# SCH_picopad_2023-12-01.net
KiCad netlist of a schematic drawn in EasyEDA
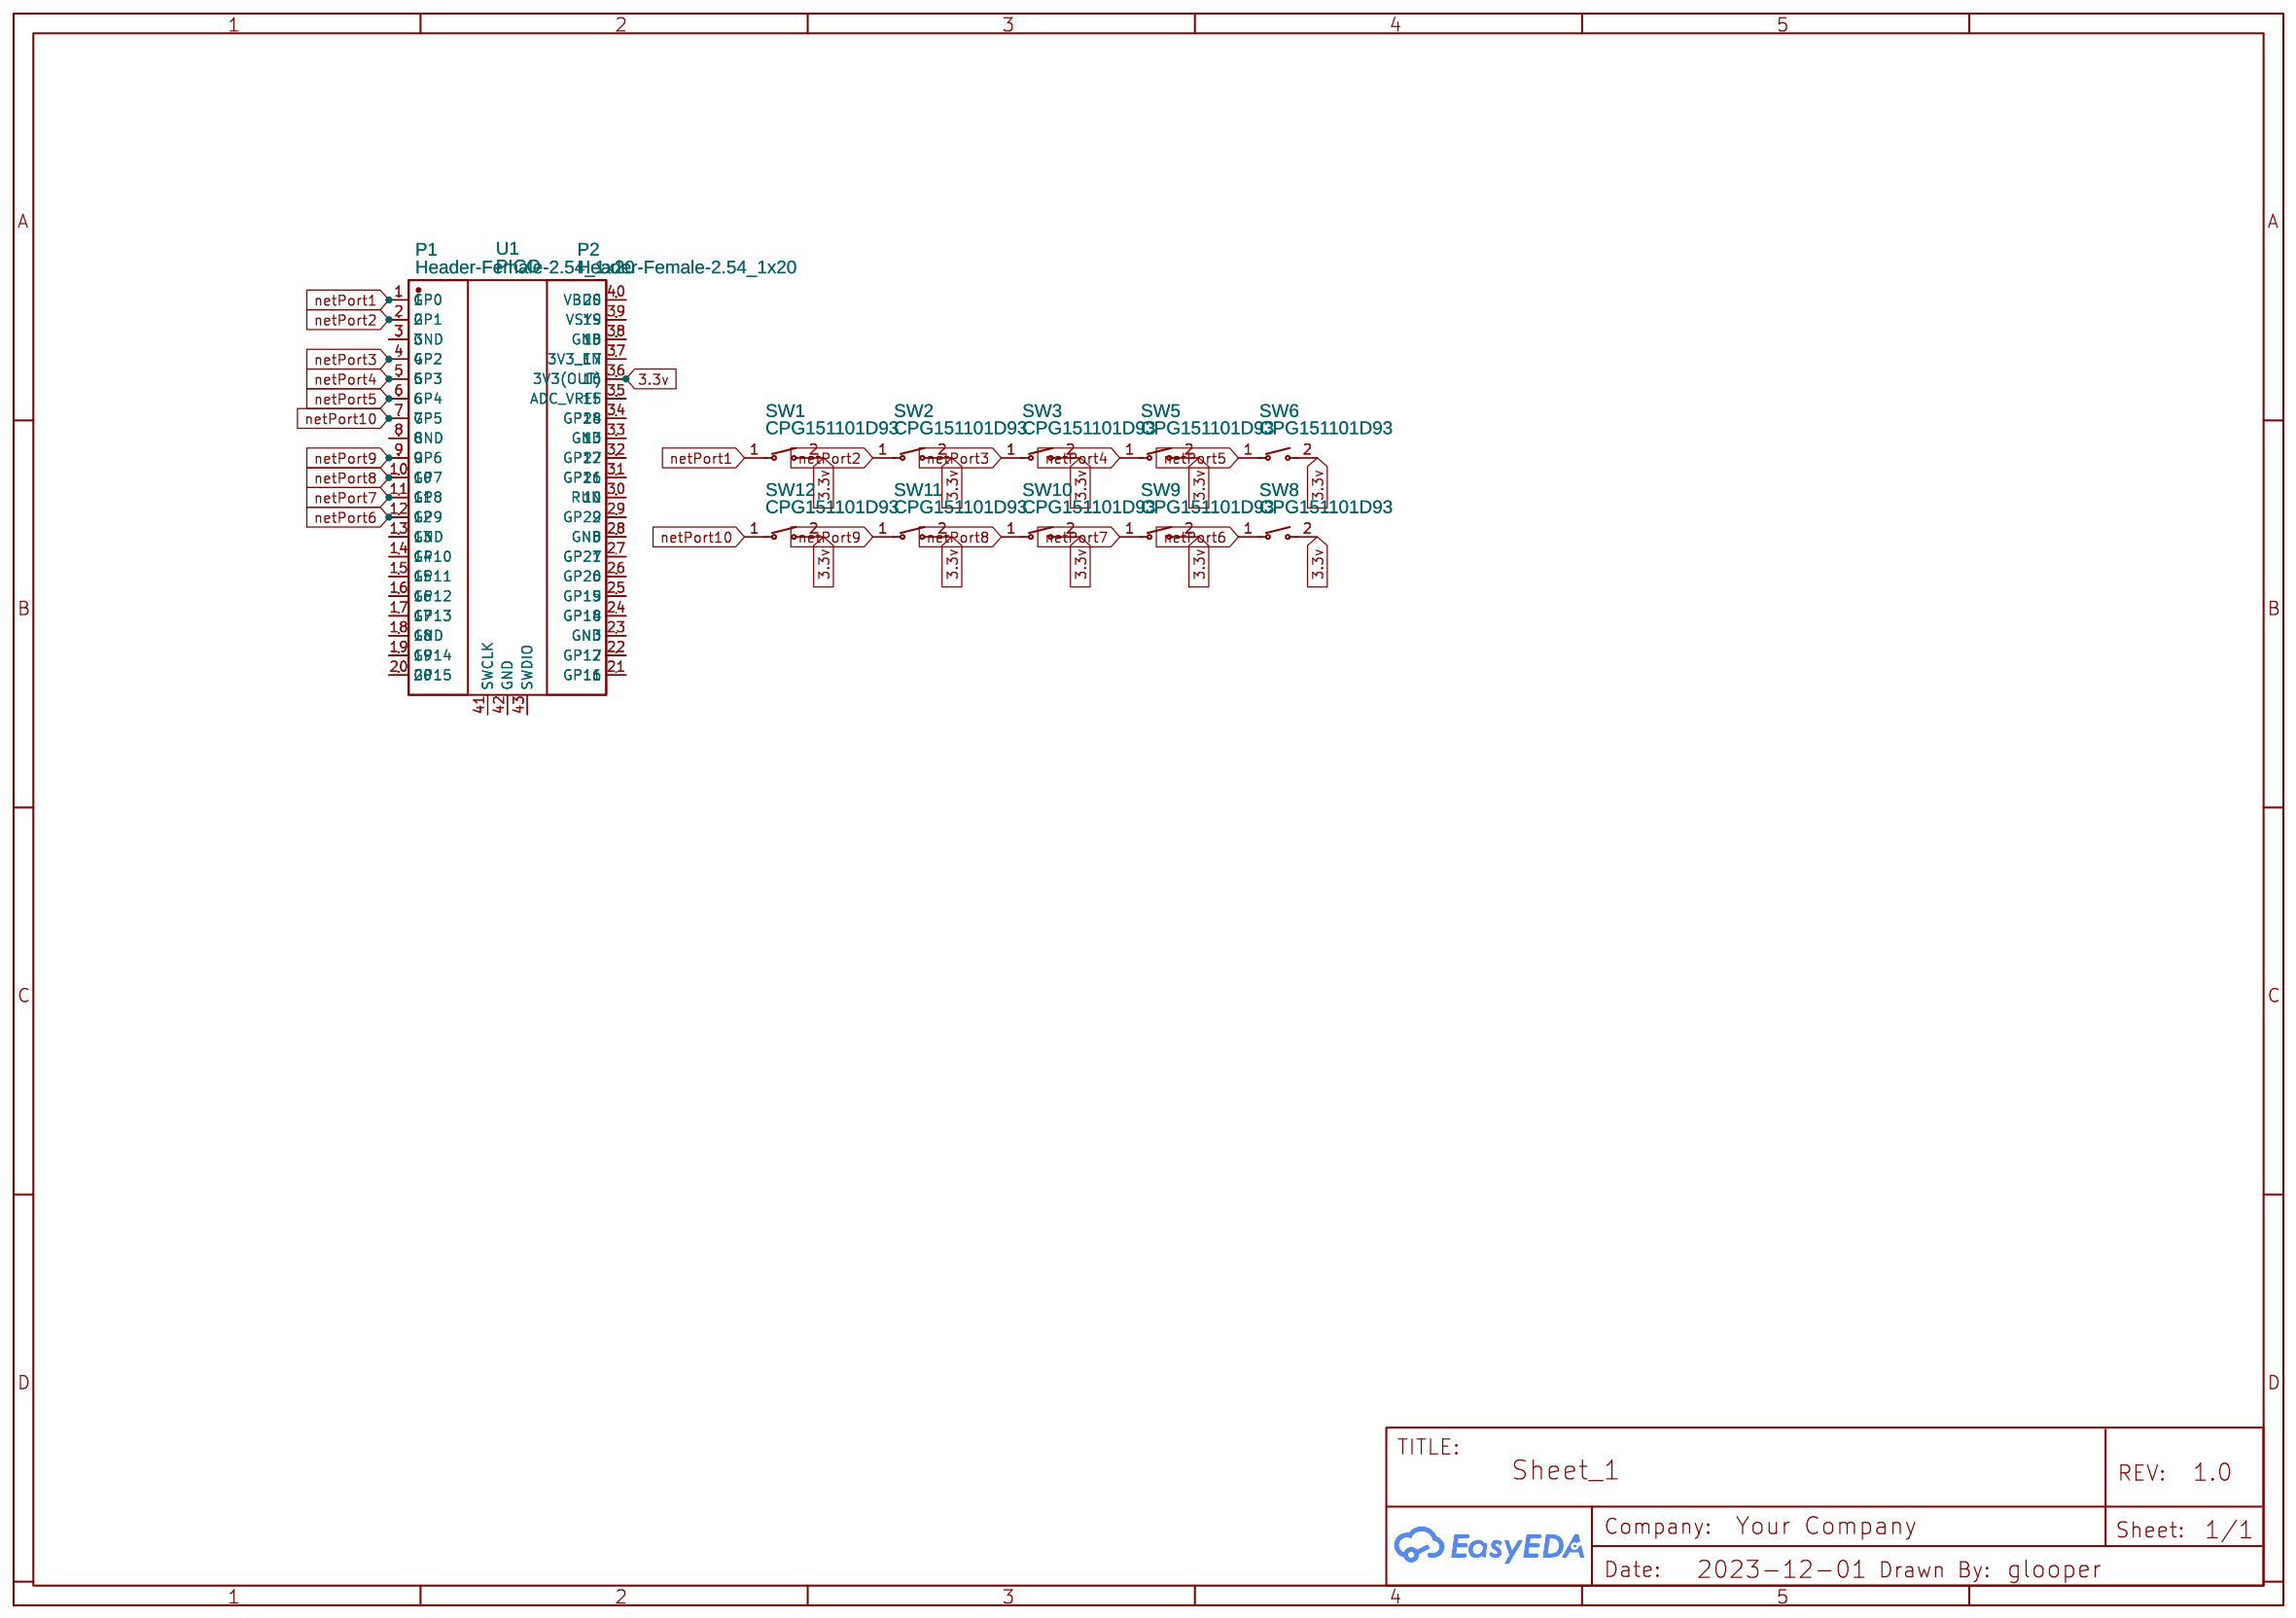
[diagram p0: schematic sheet]

(export (version "E")
  (design (tool "Eeschema 10.0.6"))
  (components
    (comp (ref "P1")
      (value "Header-Female-2.54_1x20")
      (fields (field (name "Manufacturer Part") "2.54-1*20P母") (field (name "Manufacturer") "BOOMELE(博穆精密)"))
      (libsource (lib "") (part "Header-Female-2.54_1x20_1"))
    )
    (comp (ref "P2")
      (value "Header-Female-2.54_1x20")
      (fields (field (name "Manufacturer Part") "2.54-1*20P母") (field (name "Manufacturer") "BOOMELE(博穆精密)"))
      (libsource (lib "") (part "Header-Female-2.54_1x20"))
    )
    (comp (ref "SW1")
      (value "CPG151101D93")
      (fields (field (name "Manufacturer") "Kailh(凯华)"))
      (libsource (lib "") (part "CPG151101D93"))
    )
    (comp (ref "SW2")
      (value "CPG151101D93")
      (fields (field (name "Manufacturer") "Kailh(凯华)"))
      (libsource (lib "") (part "CPG151101D93"))
    )
    (comp (ref "SW3")
      (value "CPG151101D93")
      (fields (field (name "Manufacturer") "Kailh(凯华)"))
      (libsource (lib "") (part "CPG151101D93"))
    )
    (comp (ref "SW5")
      (value "CPG151101D93")
      (fields (field (name "Manufacturer") "Kailh(凯华)"))
      (libsource (lib "") (part "CPG151101D93"))
    )
    (comp (ref "SW6")
      (value "CPG151101D93")
      (fields (field (name "Manufacturer") "Kailh(凯华)"))
      (libsource (lib "") (part "CPG151101D93"))
    )
    (comp (ref "SW8")
      (value "CPG151101D93")
      (fields (field (name "Manufacturer") "Kailh(凯华)"))
      (libsource (lib "") (part "CPG151101D93"))
    )
    (comp (ref "SW9")
      (value "CPG151101D93")
      (fields (field (name "Manufacturer") "Kailh(凯华)"))
      (libsource (lib "") (part "CPG151101D93"))
    )
    (comp (ref "SW10")
      (value "CPG151101D93")
      (fields (field (name "Manufacturer") "Kailh(凯华)"))
      (libsource (lib "") (part "CPG151101D93"))
    )
    (comp (ref "SW11")
      (value "CPG151101D93")
      (fields (field (name "Manufacturer") "Kailh(凯华)"))
      (libsource (lib "") (part "CPG151101D93"))
    )
    (comp (ref "SW12")
      (value "CPG151101D93")
      (fields (field (name "Manufacturer") "Kailh(凯华)"))
      (libsource (lib "") (part "CPG151101D93"))
    )
    (comp (ref "U1")
      (value "PICO")
      (fields (field (name "Manufacturer") "Raspberry Pi(树莓派)"))
      (libsource (lib "") (part "PICO"))
    )
  )
  (nets
    (net (code "1") (name "3.3v") (class "Default")
      (node (ref "P2") (pin "16") (pinfunction "16_16") (pintype "input"))
      (node (ref "SW1") (pin "2") (pinfunction "2_2") (pintype "unspecified"))
      (node (ref "SW10") (pin "2") (pinfunction "2_2") (pintype "unspecified"))
      (node (ref "SW11") (pin "2") (pinfunction "2_2") (pintype "unspecified"))
      (node (ref "SW12") (pin "2") (pinfunction "2_2") (pintype "unspecified"))
      (node (ref "SW2") (pin "2") (pinfunction "2_2") (pintype "unspecified"))
      (node (ref "SW3") (pin "2") (pinfunction "2_2") (pintype "unspecified"))
      (node (ref "SW5") (pin "2") (pinfunction "2_2") (pintype "unspecified"))
      (node (ref "SW6") (pin "2") (pinfunction "2_2") (pintype "unspecified"))
      (node (ref "SW8") (pin "2") (pinfunction "2_2") (pintype "unspecified"))
      (node (ref "SW9") (pin "2") (pinfunction "2_2") (pintype "unspecified"))
      (node (ref "U1") (pin "36") (pinfunction "3V3(OUT)_36") (pintype "unspecified"))
    )
    (net (code "2") (name "Net-(P1-Pad3)") (class "Default")
      (node (ref "P1") (pin "3") (pinfunction "3_3") (pintype "input"))
      (node (ref "U1") (pin "3") (pinfunction "GND_3") (pintype "unspecified"))
    )
    (net (code "3") (name "Net-(P1-Pad8)") (class "Default")
      (node (ref "P1") (pin "8") (pinfunction "8_8") (pintype "input"))
      (node (ref "U1") (pin "8") (pinfunction "GND_8") (pintype "unspecified"))
    )
    (net (code "4") (name "Net-(P1-Pad13)") (class "Default")
      (node (ref "P1") (pin "13") (pinfunction "13_13") (pintype "input"))
      (node (ref "U1") (pin "13") (pinfunction "GND_13") (pintype "unspecified"))
    )
    (net (code "5") (name "Net-(P1-Pad18)") (class "Default")
      (node (ref "P1") (pin "18") (pinfunction "18_18") (pintype "input"))
      (node (ref "U1") (pin "18") (pinfunction "GND_18") (pintype "unspecified"))
    )
    (net (code "6") (name "Net-(P2-Pad3)") (class "Default")
      (node (ref "P2") (pin "3") (pinfunction "3_3") (pintype "input"))
      (node (ref "U1") (pin "23") (pinfunction "GND_23") (pintype "unspecified"))
    )
    (net (code "7") (name "Net-(P2-Pad8)") (class "Default")
      (node (ref "P2") (pin "8") (pinfunction "8_8") (pintype "input"))
      (node (ref "U1") (pin "28") (pinfunction "GND_28") (pintype "unspecified"))
    )
    (net (code "8") (name "Net-(P2-Pad13)") (class "Default")
      (node (ref "P2") (pin "13") (pinfunction "13_13") (pintype "input"))
      (node (ref "U1") (pin "33") (pinfunction "GND_33") (pintype "unspecified"))
    )
    (net (code "9") (name "Net-(P2-Pad18)") (class "Default")
      (node (ref "P2") (pin "18") (pinfunction "18_18") (pintype "input"))
      (node (ref "U1") (pin "38") (pinfunction "GND_38") (pintype "unspecified"))
    )
    (net (code "10") (name "Net-(U1-3V3_EN)") (class "Default")
      (node (ref "P2") (pin "17") (pinfunction "17_17") (pintype "input"))
      (node (ref "U1") (pin "37") (pinfunction "3V3_EN_37") (pintype "unspecified"))
    )
    (net (code "11") (name "Net-(U1-ADC_VREF)") (class "Default")
      (node (ref "P2") (pin "15") (pinfunction "15_15") (pintype "input"))
      (node (ref "U1") (pin "35") (pinfunction "ADC_VREF_35") (pintype "unspecified"))
    )
    (net (code "12") (name "Net-(U1-GP10)") (class "Default")
      (node (ref "P1") (pin "14") (pinfunction "14_14") (pintype "input"))
      (node (ref "U1") (pin "14") (pinfunction "GP10_14") (pintype "unspecified"))
    )
    (net (code "13") (name "Net-(U1-GP11)") (class "Default")
      (node (ref "P1") (pin "15") (pinfunction "15_15") (pintype "input"))
      (node (ref "U1") (pin "15") (pinfunction "GP11_15") (pintype "unspecified"))
    )
    (net (code "14") (name "Net-(U1-GP12)") (class "Default")
      (node (ref "P1") (pin "16") (pinfunction "16_16") (pintype "input"))
      (node (ref "U1") (pin "16") (pinfunction "GP12_16") (pintype "unspecified"))
    )
    (net (code "15") (name "Net-(U1-GP13)") (class "Default")
      (node (ref "P1") (pin "17") (pinfunction "17_17") (pintype "input"))
      (node (ref "U1") (pin "17") (pinfunction "GP13_17") (pintype "unspecified"))
    )
    (net (code "16") (name "Net-(U1-GP14)") (class "Default")
      (node (ref "P1") (pin "19") (pinfunction "19_19") (pintype "input"))
      (node (ref "U1") (pin "19") (pinfunction "GP14_19") (pintype "unspecified"))
    )
    (net (code "17") (name "Net-(U1-GP15)") (class "Default")
      (node (ref "P1") (pin "20") (pinfunction "20_20") (pintype "input"))
      (node (ref "U1") (pin "20") (pinfunction "GP15_20") (pintype "unspecified"))
    )
    (net (code "18") (name "Net-(U1-GP16)") (class "Default")
      (node (ref "P2") (pin "1") (pinfunction "1_1") (pintype "input"))
      (node (ref "U1") (pin "21") (pinfunction "GP16_21") (pintype "unspecified"))
    )
    (net (code "19") (name "Net-(U1-GP17)") (class "Default")
      (node (ref "P2") (pin "2") (pinfunction "2_2") (pintype "input"))
      (node (ref "U1") (pin "22") (pinfunction "GP17_22") (pintype "unspecified"))
    )
    (net (code "20") (name "Net-(U1-GP18)") (class "Default")
      (node (ref "P2") (pin "4") (pinfunction "4_4") (pintype "input"))
      (node (ref "U1") (pin "24") (pinfunction "GP18_24") (pintype "unspecified"))
    )
    (net (code "21") (name "Net-(U1-GP19)") (class "Default")
      (node (ref "P2") (pin "5") (pinfunction "5_5") (pintype "input"))
      (node (ref "U1") (pin "25") (pinfunction "GP19_25") (pintype "unspecified"))
    )
    (net (code "22") (name "Net-(U1-GP20)") (class "Default")
      (node (ref "P2") (pin "6") (pinfunction "6_6") (pintype "input"))
      (node (ref "U1") (pin "26") (pinfunction "GP20_26") (pintype "unspecified"))
    )
    (net (code "23") (name "Net-(U1-GP21)") (class "Default")
      (node (ref "P2") (pin "7") (pinfunction "7_7") (pintype "input"))
      (node (ref "U1") (pin "27") (pinfunction "GP21_27") (pintype "unspecified"))
    )
    (net (code "24") (name "Net-(U1-GP22)") (class "Default")
      (node (ref "P2") (pin "9") (pinfunction "9_9") (pintype "input"))
      (node (ref "U1") (pin "29") (pinfunction "GP22_29") (pintype "unspecified"))
    )
    (net (code "25") (name "Net-(U1-GP26)") (class "Default")
      (node (ref "P2") (pin "11") (pinfunction "11_11") (pintype "input"))
      (node (ref "U1") (pin "31") (pinfunction "GP26_31") (pintype "unspecified"))
    )
    (net (code "26") (name "Net-(U1-GP27)") (class "Default")
      (node (ref "P2") (pin "12") (pinfunction "12_12") (pintype "input"))
      (node (ref "U1") (pin "32") (pinfunction "GP27_32") (pintype "unspecified"))
    )
    (net (code "27") (name "Net-(U1-GP28)") (class "Default")
      (node (ref "P2") (pin "14") (pinfunction "14_14") (pintype "input"))
      (node (ref "U1") (pin "34") (pinfunction "GP28_34") (pintype "unspecified"))
    )
    (net (code "28") (name "Net-(U1-RUN)") (class "Default")
      (node (ref "P2") (pin "10") (pinfunction "10_10") (pintype "input"))
      (node (ref "U1") (pin "30") (pinfunction "RUN_30") (pintype "unspecified"))
    )
    (net (code "29") (name "Net-(U1-VBUS)") (class "Default")
      (node (ref "P2") (pin "20") (pinfunction "20_20") (pintype "input"))
      (node (ref "U1") (pin "40") (pinfunction "VBUS_40") (pintype "unspecified"))
    )
    (net (code "30") (name "Net-(U1-VSYS)") (class "Default")
      (node (ref "P2") (pin "19") (pinfunction "19_19") (pintype "input"))
      (node (ref "U1") (pin "39") (pinfunction "VSYS_39") (pintype "unspecified"))
    )
    (net (code "31") (name "netPort1") (class "Default")
      (node (ref "P1") (pin "1") (pinfunction "1_1") (pintype "input"))
      (node (ref "SW1") (pin "1") (pinfunction "1_1") (pintype "unspecified"))
      (node (ref "U1") (pin "1") (pinfunction "GP0_1") (pintype "unspecified"))
    )
    (net (code "32") (name "netPort2") (class "Default")
      (node (ref "P1") (pin "2") (pinfunction "2_2") (pintype "input"))
      (node (ref "SW2") (pin "1") (pinfunction "1_1") (pintype "unspecified"))
      (node (ref "U1") (pin "2") (pinfunction "GP1_2") (pintype "unspecified"))
    )
    (net (code "33") (name "netPort3") (class "Default")
      (node (ref "P1") (pin "4") (pinfunction "4_4") (pintype "input"))
      (node (ref "SW3") (pin "1") (pinfunction "1_1") (pintype "unspecified"))
      (node (ref "U1") (pin "4") (pinfunction "GP2_4") (pintype "unspecified"))
    )
    (net (code "34") (name "netPort4") (class "Default")
      (node (ref "P1") (pin "5") (pinfunction "5_5") (pintype "input"))
      (node (ref "SW5") (pin "1") (pinfunction "1_1") (pintype "unspecified"))
      (node (ref "U1") (pin "5") (pinfunction "GP3_5") (pintype "unspecified"))
    )
    (net (code "35") (name "netPort5") (class "Default")
      (node (ref "P1") (pin "6") (pinfunction "6_6") (pintype "input"))
      (node (ref "SW6") (pin "1") (pinfunction "1_1") (pintype "unspecified"))
      (node (ref "U1") (pin "6") (pinfunction "GP4_6") (pintype "unspecified"))
    )
    (net (code "36") (name "netPort6") (class "Default")
      (node (ref "P1") (pin "12") (pinfunction "12_12") (pintype "input"))
      (node (ref "SW8") (pin "1") (pinfunction "1_1") (pintype "unspecified"))
      (node (ref "U1") (pin "12") (pinfunction "GP9_12") (pintype "unspecified"))
    )
    (net (code "37") (name "netPort7") (class "Default")
      (node (ref "P1") (pin "11") (pinfunction "11_11") (pintype "input"))
      (node (ref "SW9") (pin "1") (pinfunction "1_1") (pintype "unspecified"))
      (node (ref "U1") (pin "11") (pinfunction "GP8_11") (pintype "unspecified"))
    )
    (net (code "38") (name "netPort8") (class "Default")
      (node (ref "P1") (pin "10") (pinfunction "10_10") (pintype "input"))
      (node (ref "SW10") (pin "1") (pinfunction "1_1") (pintype "unspecified"))
      (node (ref "U1") (pin "10") (pinfunction "GP7_10") (pintype "unspecified"))
    )
    (net (code "39") (name "netPort9") (class "Default")
      (node (ref "P1") (pin "9") (pinfunction "9_9") (pintype "input"))
      (node (ref "SW11") (pin "1") (pinfunction "1_1") (pintype "unspecified"))
      (node (ref "U1") (pin "9") (pinfunction "GP6_9") (pintype "unspecified"))
    )
    (net (code "40") (name "netPort10") (class "Default")
      (node (ref "P1") (pin "7") (pinfunction "7_7") (pintype "input"))
      (node (ref "SW12") (pin "1") (pinfunction "1_1") (pintype "unspecified"))
      (node (ref "U1") (pin "7") (pinfunction "GP5_7") (pintype "unspecified"))
    )
    (net (code "41") (name "unconnected-(U1-GND-Pad42)") (class "Default")
      (node (ref "U1") (pin "42") (pinfunction "GND_42") (pintype "unspecified"))
    )
    (net (code "42") (name "unconnected-(U1-SWCLK-Pad41)") (class "Default")
      (node (ref "U1") (pin "41") (pinfunction "SWCLK_41") (pintype "unspecified"))
    )
    (net (code "43") (name "unconnected-(U1-SWDIO-Pad43)") (class "Default")
      (node (ref "U1") (pin "43") (pinfunction "SWDIO_43") (pintype "unspecified"))
    )
  )
)
